# EEProm_writer_easyeda.net
KiCad netlist of a schematic drawn in EasyEDA
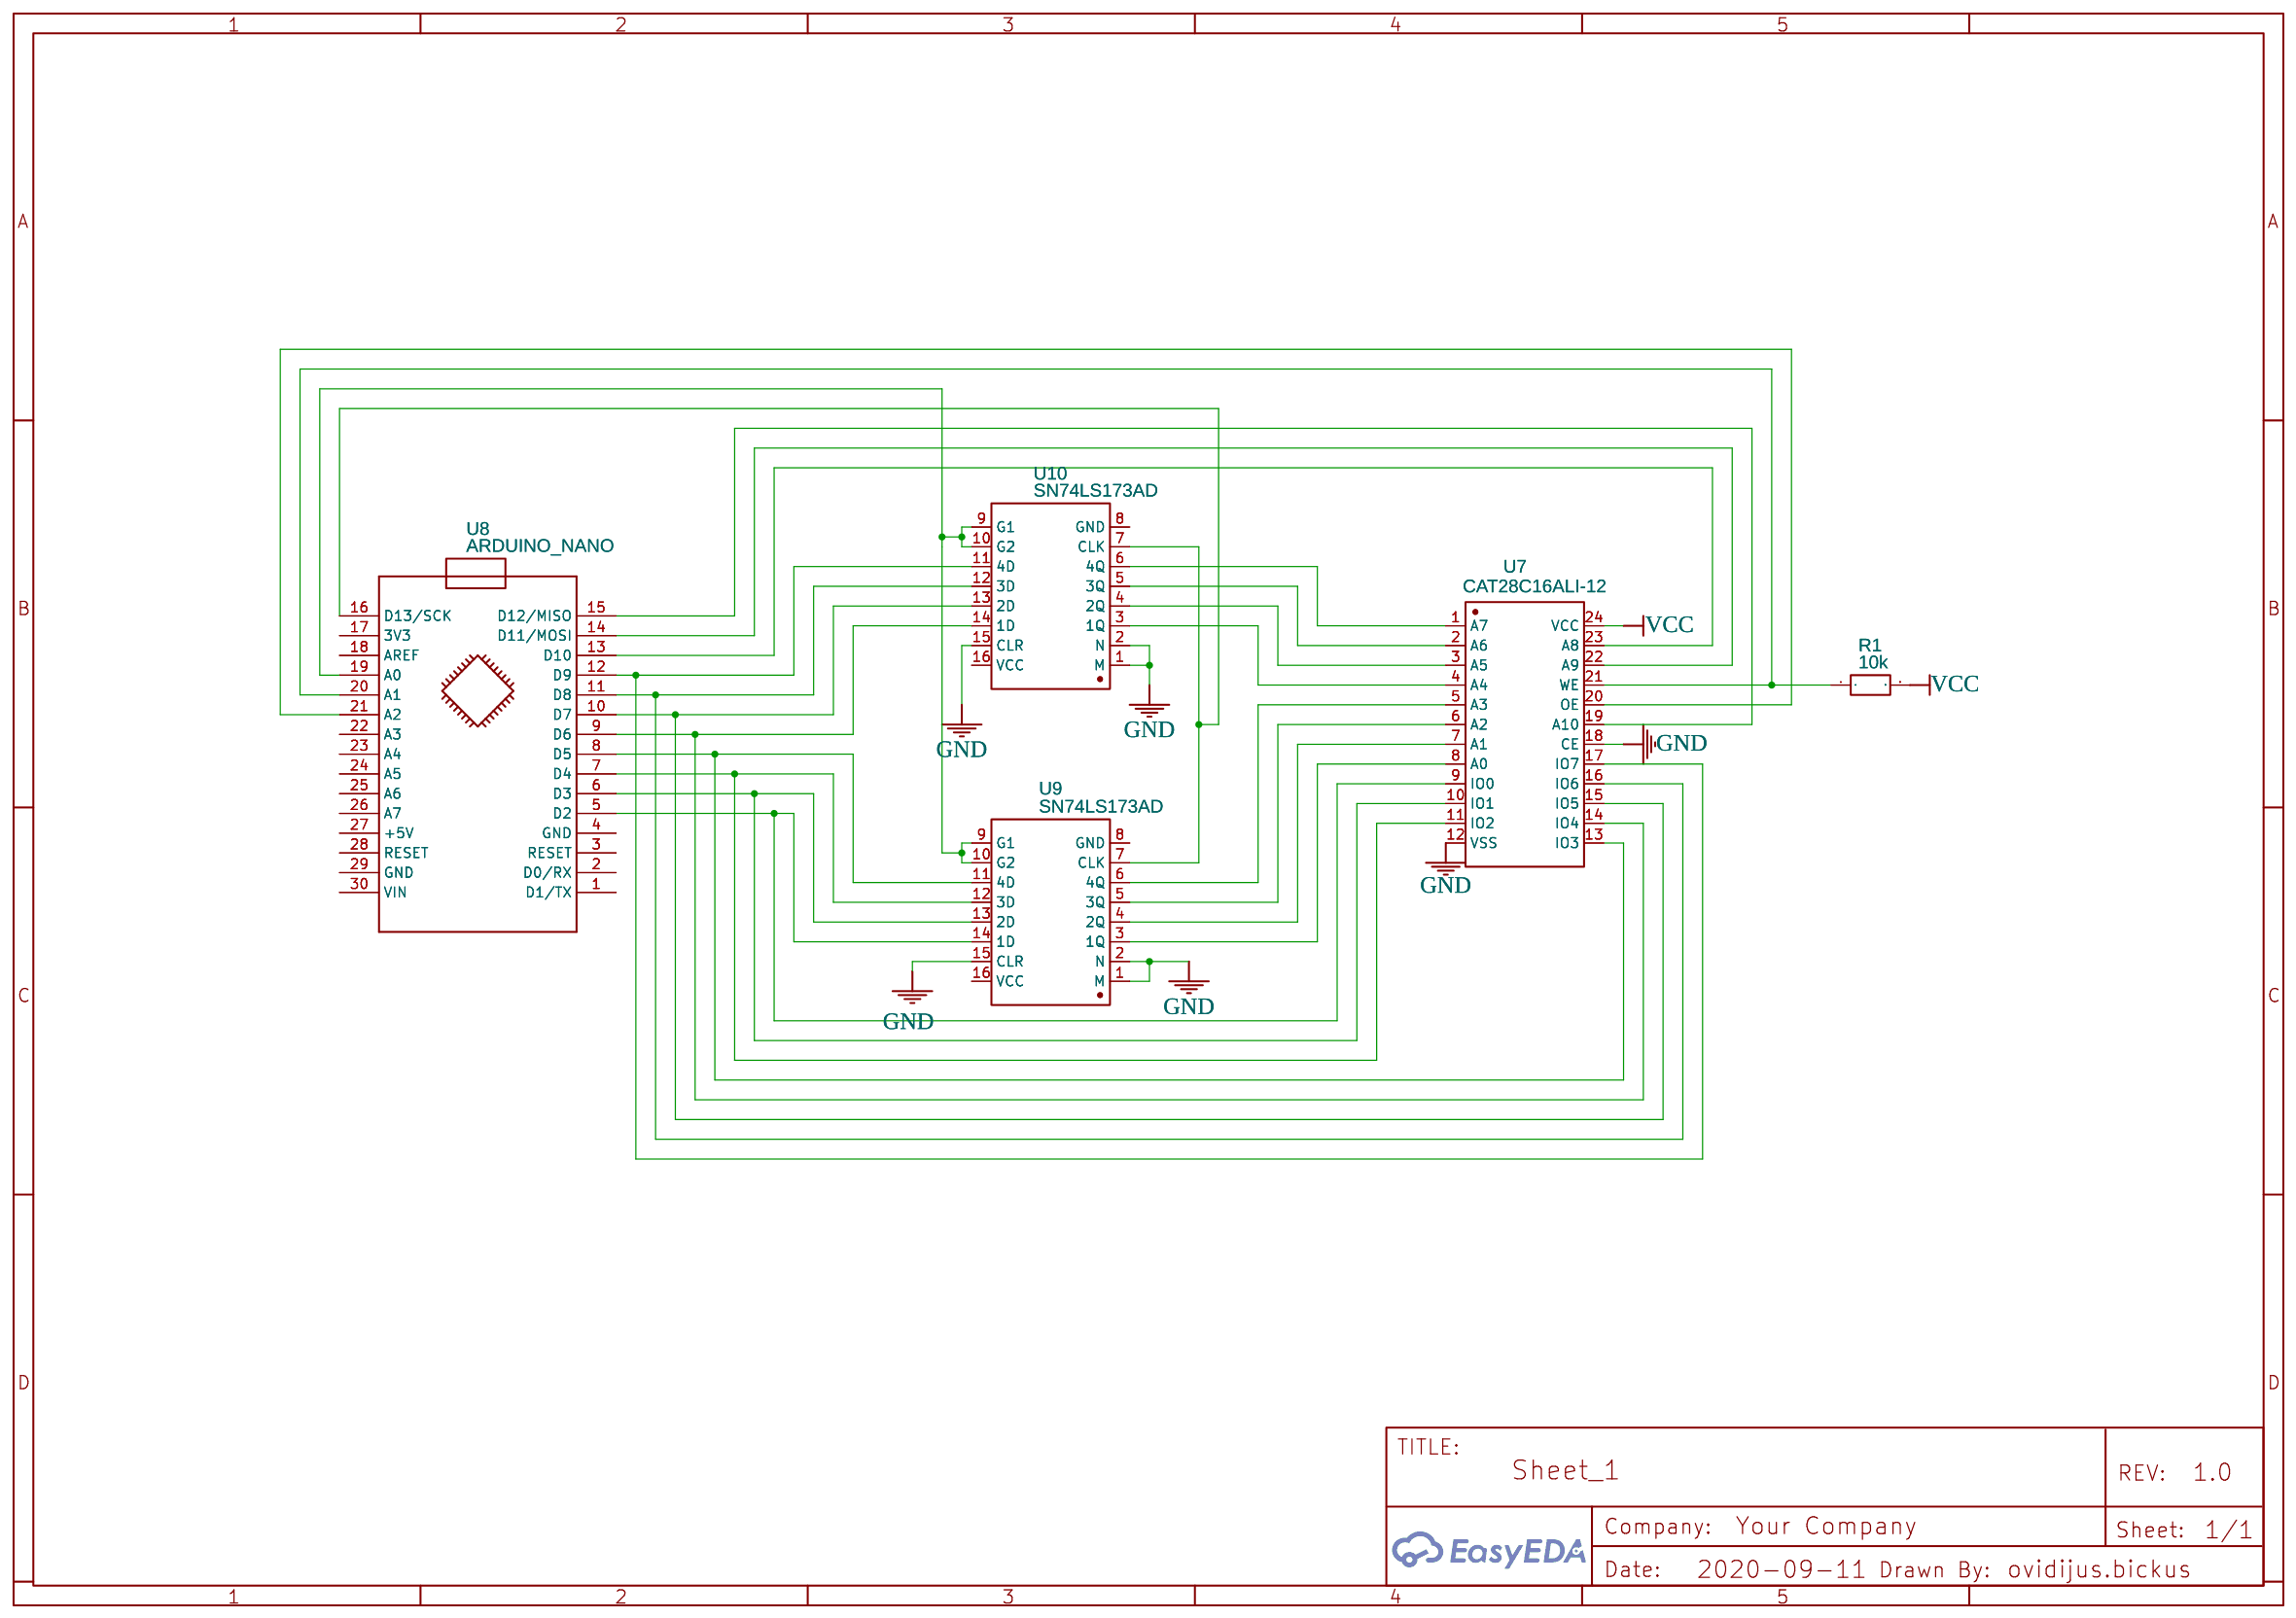
[diagram p0: schematic sheet]

(export (version "E")
  (design (tool "Eeschema 10.0.6"))
  (components
    (comp (ref "R1") (value "10k") (libsource (lib "") (part "R_0603_EU")))
    (comp (ref "U7") (value "CAT28C16ALI-12") (libsource (lib "") (part "CAT28C16ALI-12")))
    (comp (ref "U8") (value "ARDUINO_NANO") (libsource (lib "") (part "ARDUINO_NANO")))
    (comp (ref "U9") (value "SN74LS173AD") (libsource (lib "") (part "SN74LS173AD")))
    (comp (ref "U10") (value "SN74LS173AD") (libsource (lib "") (part "SN74LS173AD")))
  )
  (nets
    (net (code "1") (name "GND") (class "Default")
      (node (ref "U10") (pin "1") (pinfunction "M_1") (pintype "unspecified"))
      (node (ref "U10") (pin "15") (pinfunction "CLR_15") (pintype "unspecified"))
      (node (ref "U10") (pin "2") (pinfunction "N_2") (pintype "unspecified"))
      (node (ref "U7") (pin "12") (pinfunction "VSS_12") (pintype "unspecified"))
      (node (ref "U7") (pin "18") (pinfunction "CE_18") (pintype "unspecified"))
      (node (ref "U9") (pin "1") (pinfunction "M_1") (pintype "unspecified"))
      (node (ref "U9") (pin "15") (pinfunction "CLR_15") (pintype "unspecified"))
      (node (ref "U9") (pin "2") (pinfunction "N_2") (pintype "unspecified"))
    )
    (net (code "2") (name "Net-(U7-A0)") (class "Default")
      (node (ref "U7") (pin "8") (pinfunction "A0_8") (pintype "unspecified"))
      (node (ref "U9") (pin "3") (pinfunction "1Q_3") (pintype "unspecified"))
    )
    (net (code "3") (name "Net-(U7-A1)") (class "Default")
      (node (ref "U7") (pin "7") (pinfunction "A1_7") (pintype "unspecified"))
      (node (ref "U9") (pin "4") (pinfunction "2Q_4") (pintype "unspecified"))
    )
    (net (code "4") (name "Net-(U7-A2)") (class "Default")
      (node (ref "U7") (pin "6") (pinfunction "A2_6") (pintype "unspecified"))
      (node (ref "U9") (pin "5") (pinfunction "3Q_5") (pintype "unspecified"))
    )
    (net (code "5") (name "Net-(U7-A3)") (class "Default")
      (node (ref "U7") (pin "5") (pinfunction "A3_5") (pintype "unspecified"))
      (node (ref "U9") (pin "6") (pinfunction "4Q_6") (pintype "unspecified"))
    )
    (net (code "6") (name "Net-(U7-A8)") (class "Default")
      (node (ref "U7") (pin "23") (pinfunction "A8_23") (pintype "unspecified"))
      (node (ref "U8") (pin "13") (pinfunction "D10_13") (pintype "unspecified"))
    )
    (net (code "7") (name "Net-(U7-A9)") (class "Default")
      (node (ref "U7") (pin "22") (pinfunction "A9_22") (pintype "unspecified"))
      (node (ref "U8") (pin "14") (pinfunction "D11/MOSI_14") (pintype "unspecified"))
    )
    (net (code "8") (name "Net-(U7-A10)") (class "Default")
      (node (ref "U7") (pin "19") (pinfunction "A10_19") (pintype "unspecified"))
      (node (ref "U8") (pin "15") (pinfunction "D12/MISO_15") (pintype "unspecified"))
    )
    (net (code "9") (name "Net-(U7-IO0)") (class "Default")
      (node (ref "U7") (pin "9") (pinfunction "IO0_9") (pintype "unspecified"))
      (node (ref "U8") (pin "5") (pinfunction "D2_5") (pintype "unspecified"))
      (node (ref "U9") (pin "14") (pinfunction "1D_14") (pintype "unspecified"))
    )
    (net (code "10") (name "Net-(U7-IO1)") (class "Default")
      (node (ref "U7") (pin "10") (pinfunction "IO1_10") (pintype "unspecified"))
      (node (ref "U8") (pin "6") (pinfunction "D3_6") (pintype "unspecified"))
      (node (ref "U9") (pin "13") (pinfunction "2D_13") (pintype "unspecified"))
    )
    (net (code "11") (name "Net-(U7-IO2)") (class "Default")
      (node (ref "U7") (pin "11") (pinfunction "IO2_11") (pintype "unspecified"))
      (node (ref "U8") (pin "7") (pinfunction "D4_7") (pintype "unspecified"))
      (node (ref "U9") (pin "12") (pinfunction "3D_12") (pintype "unspecified"))
    )
    (net (code "12") (name "Net-(U7-IO3)") (class "Default")
      (node (ref "U7") (pin "13") (pinfunction "IO3_13") (pintype "unspecified"))
      (node (ref "U8") (pin "8") (pinfunction "D5_8") (pintype "unspecified"))
      (node (ref "U9") (pin "11") (pinfunction "4D_11") (pintype "unspecified"))
    )
    (net (code "13") (name "Net-(U7-OE)") (class "Default")
      (node (ref "U7") (pin "20") (pinfunction "OE_20") (pintype "unspecified"))
      (node (ref "U8") (pin "21") (pinfunction "A2_21") (pintype "unspecified"))
    )
    (net (code "14") (name "Net-(U7-WE)") (class "Default")
      (node (ref "R1") (pin "1") (pinfunction "1_1") (pintype "unspecified"))
      (node (ref "U7") (pin "21") (pinfunction "WE_21") (pintype "unspecified"))
      (node (ref "U8") (pin "20") (pinfunction "A1_20") (pintype "unspecified"))
    )
    (net (code "15") (name "Net-(U10-1D)") (class "Default")
      (node (ref "U10") (pin "14") (pinfunction "1D_14") (pintype "unspecified"))
      (node (ref "U7") (pin "14") (pinfunction "IO4_14") (pintype "unspecified"))
      (node (ref "U8") (pin "9") (pinfunction "D6_9") (pintype "unspecified"))
    )
    (net (code "16") (name "Net-(U10-1Q)") (class "Default")
      (node (ref "U10") (pin "3") (pinfunction "1Q_3") (pintype "unspecified"))
      (node (ref "U7") (pin "4") (pinfunction "A4_4") (pintype "unspecified"))
    )
    (net (code "17") (name "Net-(U10-2D)") (class "Default")
      (node (ref "U10") (pin "13") (pinfunction "2D_13") (pintype "unspecified"))
      (node (ref "U7") (pin "15") (pinfunction "IO5_15") (pintype "unspecified"))
      (node (ref "U8") (pin "10") (pinfunction "D7_10") (pintype "unspecified"))
    )
    (net (code "18") (name "Net-(U10-2Q)") (class "Default")
      (node (ref "U10") (pin "4") (pinfunction "2Q_4") (pintype "unspecified"))
      (node (ref "U7") (pin "3") (pinfunction "A5_3") (pintype "unspecified"))
    )
    (net (code "19") (name "Net-(U10-3D)") (class "Default")
      (node (ref "U10") (pin "12") (pinfunction "3D_12") (pintype "unspecified"))
      (node (ref "U7") (pin "16") (pinfunction "IO6_16") (pintype "unspecified"))
      (node (ref "U8") (pin "11") (pinfunction "D8_11") (pintype "unspecified"))
    )
    (net (code "20") (name "Net-(U10-3Q)") (class "Default")
      (node (ref "U10") (pin "5") (pinfunction "3Q_5") (pintype "unspecified"))
      (node (ref "U7") (pin "2") (pinfunction "A6_2") (pintype "unspecified"))
    )
    (net (code "21") (name "Net-(U10-4D)") (class "Default")
      (node (ref "U10") (pin "11") (pinfunction "4D_11") (pintype "unspecified"))
      (node (ref "U7") (pin "17") (pinfunction "IO7_17") (pintype "unspecified"))
      (node (ref "U8") (pin "12") (pinfunction "D9_12") (pintype "unspecified"))
    )
    (net (code "22") (name "Net-(U10-4Q)") (class "Default")
      (node (ref "U10") (pin "6") (pinfunction "4Q_6") (pintype "unspecified"))
      (node (ref "U7") (pin "1") (pinfunction "A7_1") (pintype "unspecified"))
    )
    (net (code "23") (name "Net-(U10-CLK)") (class "Default")
      (node (ref "U10") (pin "7") (pinfunction "CLK_7") (pintype "unspecified"))
      (node (ref "U8") (pin "16") (pinfunction "D13/SCK_16") (pintype "unspecified"))
      (node (ref "U9") (pin "7") (pinfunction "CLK_7") (pintype "unspecified"))
    )
    (net (code "24") (name "Net-(U10-G1)") (class "Default")
      (node (ref "U10") (pin "10") (pinfunction "G2_10") (pintype "unspecified"))
      (node (ref "U10") (pin "9") (pinfunction "G1_9") (pintype "unspecified"))
      (node (ref "U8") (pin "19") (pinfunction "A0_19") (pintype "unspecified"))
      (node (ref "U9") (pin "10") (pinfunction "G2_10") (pintype "unspecified"))
      (node (ref "U9") (pin "9") (pinfunction "G1_9") (pintype "unspecified"))
    )
    (net (code "25") (name "VCC") (class "Default")
      (node (ref "R1") (pin "2") (pinfunction "2_2") (pintype "unspecified"))
      (node (ref "U7") (pin "24") (pinfunction "VCC_24") (pintype "unspecified"))
    )
    (net (code "26") (name "unconnected-(U8-+5V-Pad27)") (class "Default")
      (node (ref "U8") (pin "27") (pinfunction "+5V_27") (pintype "unspecified"))
    )
    (net (code "27") (name "unconnected-(U8-3V3-Pad17)") (class "Default")
      (node (ref "U8") (pin "17") (pinfunction "3V3_17") (pintype "unspecified"))
    )
    (net (code "28") (name "unconnected-(U8-A3-Pad22)") (class "Default")
      (node (ref "U8") (pin "22") (pinfunction "A3_22") (pintype "unspecified"))
    )
    (net (code "29") (name "unconnected-(U8-A4-Pad23)") (class "Default")
      (node (ref "U8") (pin "23") (pinfunction "A4_23") (pintype "unspecified"))
    )
    (net (code "30") (name "unconnected-(U8-A5-Pad24)") (class "Default")
      (node (ref "U8") (pin "24") (pinfunction "A5_24") (pintype "unspecified"))
    )
    (net (code "31") (name "unconnected-(U8-A6-Pad25)") (class "Default")
      (node (ref "U8") (pin "25") (pinfunction "A6_25") (pintype "unspecified"))
    )
    (net (code "32") (name "unconnected-(U8-A7-Pad26)") (class "Default")
      (node (ref "U8") (pin "26") (pinfunction "A7_26") (pintype "unspecified"))
    )
    (net (code "33") (name "unconnected-(U8-AREF-Pad18)") (class "Default")
      (node (ref "U8") (pin "18") (pinfunction "AREF_18") (pintype "unspecified"))
    )
    (net (code "34") (name "unconnected-(U8-D0{slash}RX-Pad2)") (class "Default")
      (node (ref "U8") (pin "2") (pinfunction "D0/RX_2") (pintype "unspecified"))
    )
    (net (code "35") (name "unconnected-(U8-D1{slash}TX-Pad1)") (class "Default")
      (node (ref "U8") (pin "1") (pinfunction "D1/TX_1") (pintype "unspecified"))
    )
    (net (code "36") (name "unconnected-(U8-GND-Pad4)") (class "Default")
      (node (ref "U8") (pin "4") (pinfunction "GND_4") (pintype "unspecified"))
    )
    (net (code "37") (name "unconnected-(U8-GND-Pad29)") (class "Default")
      (node (ref "U8") (pin "29") (pinfunction "GND_29") (pintype "unspecified"))
    )
    (net (code "38") (name "unconnected-(U8-RESET-Pad3)") (class "Default")
      (node (ref "U8") (pin "3") (pinfunction "RESET_3") (pintype "unspecified"))
    )
    (net (code "39") (name "unconnected-(U8-RESET-Pad28)") (class "Default")
      (node (ref "U8") (pin "28") (pinfunction "RESET_28") (pintype "unspecified"))
    )
    (net (code "40") (name "unconnected-(U8-VIN-Pad30)") (class "Default")
      (node (ref "U8") (pin "30") (pinfunction "VIN_30") (pintype "unspecified"))
    )
    (net (code "41") (name "unconnected-(U9-GND-Pad8)") (class "Default")
      (node (ref "U9") (pin "8") (pinfunction "GND_8") (pintype "unspecified"))
    )
    (net (code "42") (name "unconnected-(U9-VCC-Pad16)") (class "Default")
      (node (ref "U9") (pin "16") (pinfunction "VCC_16") (pintype "unspecified"))
    )
    (net (code "43") (name "unconnected-(U10-GND-Pad8)") (class "Default")
      (node (ref "U10") (pin "8") (pinfunction "GND_8") (pintype "unspecified"))
    )
    (net (code "44") (name "unconnected-(U10-VCC-Pad16)") (class "Default")
      (node (ref "U10") (pin "16") (pinfunction "VCC_16") (pintype "unspecified"))
    )
  )
)
